# OPs.net
KiCad netlist of a schematic drawn in Altium Designer
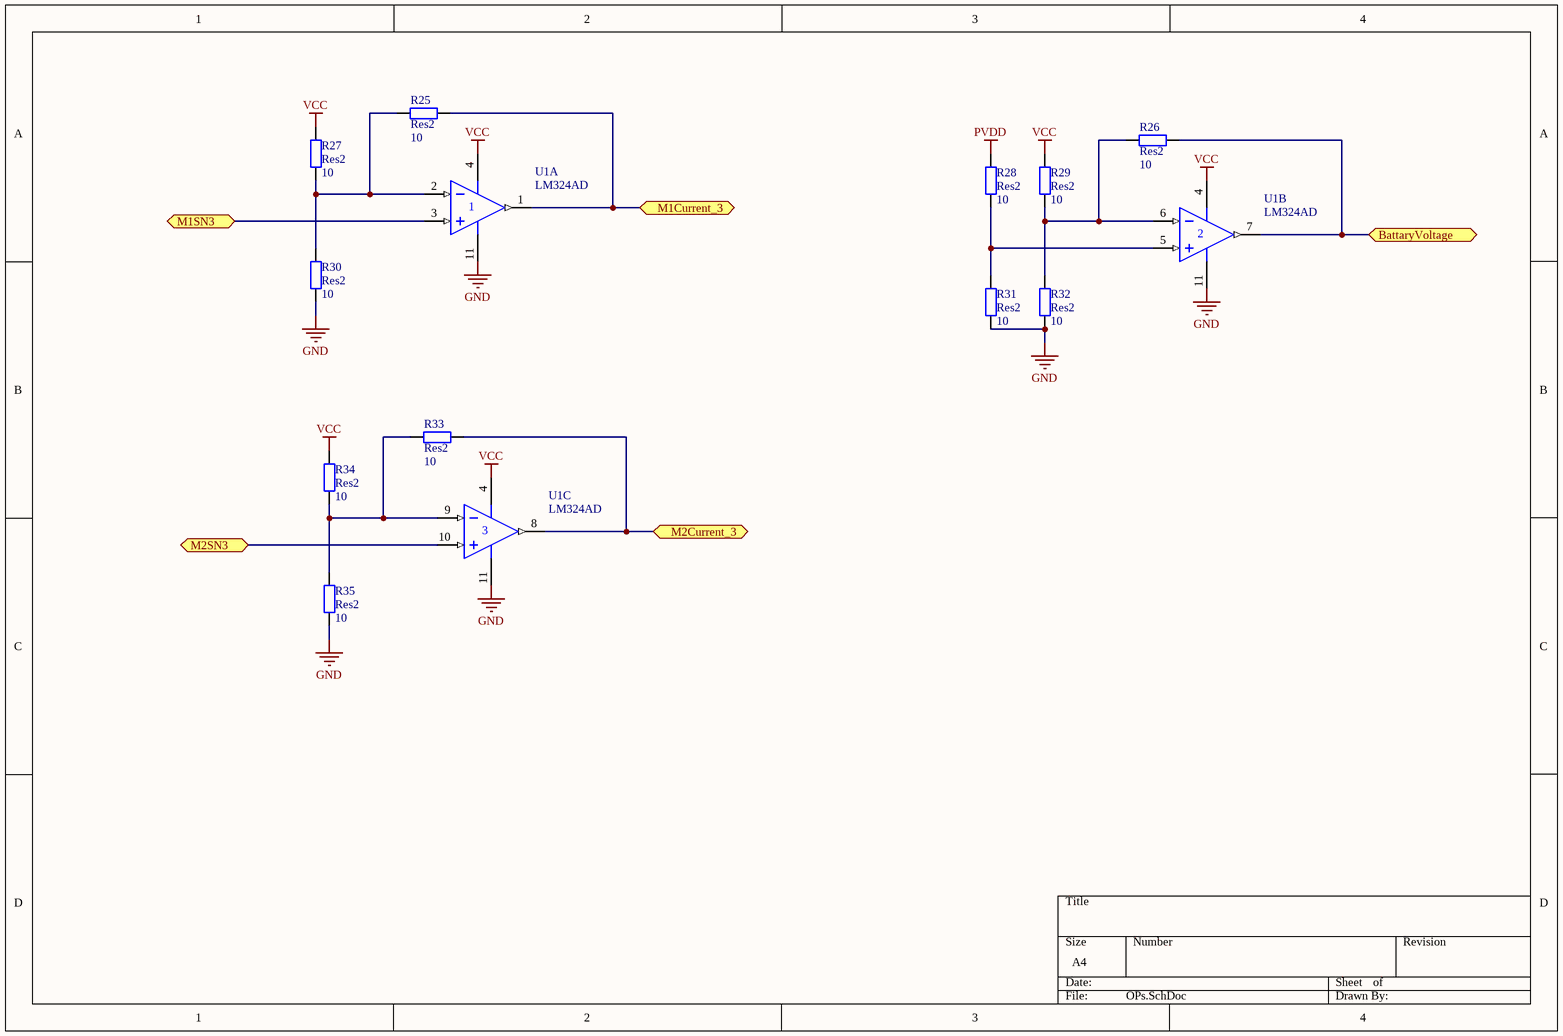
[diagram p0: OPs.SchDoc]

(export (version "E")
  (design (tool "Eeschema 10.0.6"))
  (components
    (comp (ref "R25")
      (value "Res2")
      (footprint "6-0805_N")
      (description "Resistor")
      (fields (field (name "ALTIUM_VALUE") "10") (field (name "PUBLISHER") "Altium Limited"))
      (libsource (lib "") (part "Res2_1"))
    )
    (comp (ref "R26")
      (value "Res2")
      (footprint "6-0805_N")
      (description "Resistor")
      (fields (field (name "ALTIUM_VALUE") "10") (field (name "PUBLISHER") "Altium Limited"))
      (libsource (lib "") (part "Res2_1"))
    )
    (comp (ref "R27")
      (value "Res2")
      (footprint "6-0805_N")
      (description "Resistor")
      (fields (field (name "ALTIUM_VALUE") "10") (field (name "PUBLISHER") "Altium Limited"))
      (libsource (lib "Miscellaneous Devices") (part "Res2"))
    )
    (comp (ref "R28")
      (value "Res2")
      (footprint "6-0805_N")
      (description "Resistor")
      (fields (field (name "ALTIUM_VALUE") "10") (field (name "PUBLISHER") "Altium Limited"))
      (libsource (lib "Miscellaneous Devices") (part "Res2"))
    )
    (comp (ref "R29")
      (value "Res2")
      (footprint "6-0805_N")
      (description "Resistor")
      (fields (field (name "ALTIUM_VALUE") "10") (field (name "PUBLISHER") "Altium Limited"))
      (libsource (lib "Miscellaneous Devices") (part "Res2"))
    )
    (comp (ref "R30")
      (value "Res2")
      (footprint "6-0805_N")
      (description "Resistor")
      (fields (field (name "ALTIUM_VALUE") "10") (field (name "PUBLISHER") "Altium Limited"))
      (libsource (lib "Miscellaneous Devices") (part "Res2"))
    )
    (comp (ref "R31")
      (value "Res2")
      (footprint "6-0805_N")
      (description "Resistor")
      (fields (field (name "ALTIUM_VALUE") "10") (field (name "PUBLISHER") "Altium Limited"))
      (libsource (lib "Miscellaneous Devices") (part "Res2"))
    )
    (comp (ref "R32")
      (value "Res2")
      (footprint "6-0805_N")
      (description "Resistor")
      (fields (field (name "ALTIUM_VALUE") "10") (field (name "PUBLISHER") "Altium Limited"))
      (libsource (lib "Miscellaneous Devices") (part "Res2"))
    )
    (comp (ref "R33")
      (value "Res2")
      (footprint "6-0805_N")
      (description "Resistor")
      (fields (field (name "ALTIUM_VALUE") "10") (field (name "PUBLISHER") "Altium Limited"))
      (libsource (lib "") (part "Res2_1"))
    )
    (comp (ref "R34")
      (value "Res2")
      (footprint "6-0805_N")
      (description "Resistor")
      (fields (field (name "ALTIUM_VALUE") "10") (field (name "PUBLISHER") "Altium Limited"))
      (libsource (lib "Miscellaneous Devices") (part "Res2"))
    )
    (comp (ref "R35")
      (value "Res2")
      (footprint "6-0805_N")
      (description "Resistor")
      (fields (field (name "ALTIUM_VALUE") "10") (field (name "PUBLISHER") "Altium Limited"))
      (libsource (lib "Miscellaneous Devices") (part "Res2"))
    )
    (comp (ref "U1")
      (value "LM324AD")
      (footprint "751A-02_N")
      (description "Quad Low-Power Operational Amplifier")
      (fields (field (name "PUBLISHER") "Altium Limited"))
      (libsource (lib "STRobot") (part "LM324AD"))
    )
  )
  (nets
    (net (code "1") (name "/BattaryVoltage") (class "Default")
      (node (ref "R26") (pin "2") (pinfunction "2_2") (pintype "passive"))
      (node (ref "U1") (pin "7") (pinfunction "OUT_7") (pintype "output"))
    )
    (net (code "2") (name "/M1Current_3") (class "Default")
      (node (ref "R25") (pin "2") (pinfunction "2_2") (pintype "passive"))
      (node (ref "U1") (pin "1") (pinfunction "OUT_1") (pintype "output"))
    )
    (net (code "3") (name "/M1SN3") (class "Default")
      (node (ref "U1") (pin "3") (pinfunction "IN+_3") (pintype "input"))
    )
    (net (code "4") (name "/M2Current_3") (class "Default")
      (node (ref "R33") (pin "2") (pinfunction "2_2") (pintype "passive"))
      (node (ref "U1") (pin "8") (pinfunction "OUT_8") (pintype "output"))
    )
    (net (code "5") (name "/M2SN3") (class "Default")
      (node (ref "U1") (pin "10") (pinfunction "IN+_10") (pintype "input"))
    )
    (net (code "6") (name "GND") (class "Default")
      (node (ref "R30") (pin "1") (pinfunction "1_1") (pintype "passive"))
      (node (ref "R31") (pin "1") (pinfunction "1_1") (pintype "passive"))
      (node (ref "R32") (pin "1") (pinfunction "1_1") (pintype "passive"))
      (node (ref "R35") (pin "1") (pinfunction "1_1") (pintype "passive"))
      (node (ref "U1") (pin "11") (pinfunction "V-_11") (pintype "power_in"))
    )
    (net (code "7") (name "Net-(U1A-IN-)") (class "Default")
      (node (ref "R25") (pin "1") (pinfunction "1_1") (pintype "passive"))
      (node (ref "R27") (pin "1") (pinfunction "1_1") (pintype "passive"))
      (node (ref "R30") (pin "2") (pinfunction "2_2") (pintype "passive"))
      (node (ref "U1") (pin "2") (pinfunction "IN-_2") (pintype "input"))
    )
    (net (code "8") (name "Net-(U1B-IN+)") (class "Default")
      (node (ref "R28") (pin "1") (pinfunction "1_1") (pintype "passive"))
      (node (ref "R31") (pin "2") (pinfunction "2_2") (pintype "passive"))
      (node (ref "U1") (pin "5") (pinfunction "IN+_5") (pintype "input"))
    )
    (net (code "9") (name "Net-(U1B-IN-)") (class "Default")
      (node (ref "R26") (pin "1") (pinfunction "1_1") (pintype "passive"))
      (node (ref "R29") (pin "1") (pinfunction "1_1") (pintype "passive"))
      (node (ref "R32") (pin "2") (pinfunction "2_2") (pintype "passive"))
      (node (ref "U1") (pin "6") (pinfunction "IN-_6") (pintype "input"))
    )
    (net (code "10") (name "Net-(U1C-IN-)") (class "Default")
      (node (ref "R33") (pin "1") (pinfunction "1_1") (pintype "passive"))
      (node (ref "R34") (pin "1") (pinfunction "1_1") (pintype "passive"))
      (node (ref "R35") (pin "2") (pinfunction "2_2") (pintype "passive"))
      (node (ref "U1") (pin "9") (pinfunction "IN-_9") (pintype "input"))
    )
    (net (code "11") (name "PVDD") (class "Default")
      (node (ref "R28") (pin "2") (pinfunction "2_2") (pintype "passive"))
    )
    (net (code "12") (name "VCC") (class "Default")
      (node (ref "R27") (pin "2") (pinfunction "2_2") (pintype "passive"))
      (node (ref "R29") (pin "2") (pinfunction "2_2") (pintype "passive"))
      (node (ref "R34") (pin "2") (pinfunction "2_2") (pintype "passive"))
      (node (ref "U1") (pin "4") (pinfunction "V+_4") (pintype "power_in"))
    )
  )
)
